# Sheet1.net
KiCad netlist of a schematic drawn in Altium Designer
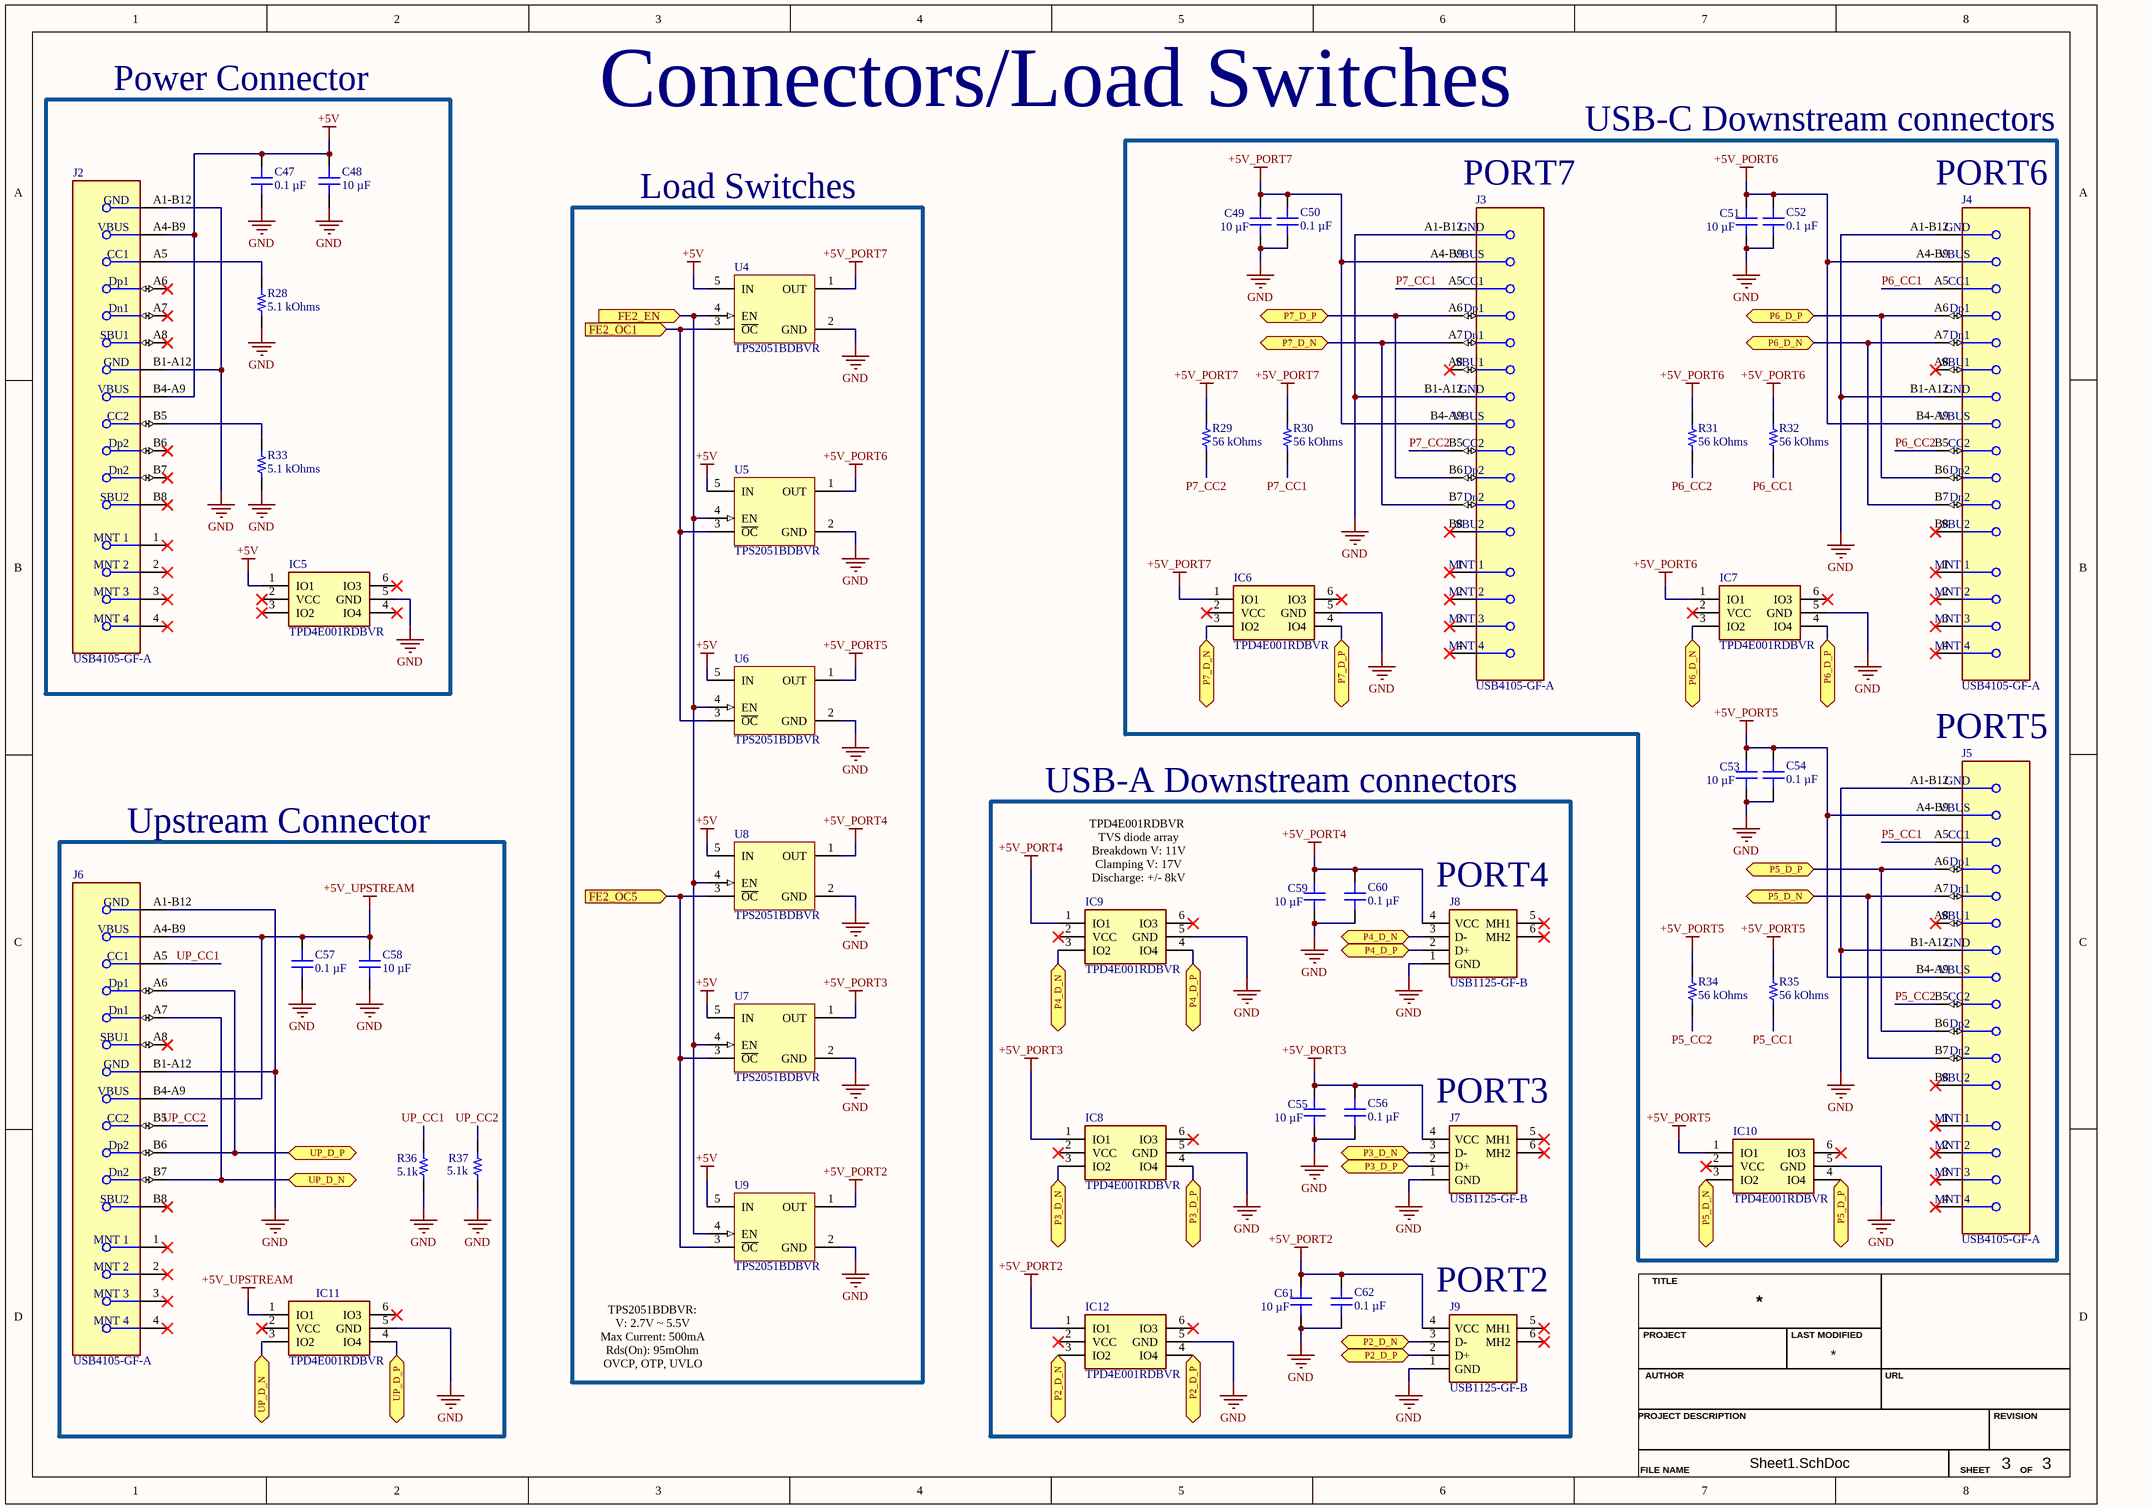
[diagram p0: Sheet1.SchDoc]

(export (version "E")
  (design (tool "Eeschema 10.0.6"))
  (components
    (comp (ref "C47")
      (value "0.1 µF")
      (footprint "CAP 0603_1608")
      (description "CAP CER 0.1UF 50V X7R 0603")
      (fields
        (field (name "PART NUMBER") "GCJ188R71H104KA12D")
        (field (name "CAPACITANCE") "0.1 µF")
        (field (name "MANUFACTURER") "Murata Electronics")
      )
      (libsource (lib "Celestial Altium Library - altium_library") (part "Capacitor"))
    )
    (comp (ref "C48")
      (value "10 µF")
      (footprint "MURATA GRM21B 0805_2012")
      (description "CAP CER 10UF 25V X5R 0805")
      (fields
        (field (name "PART NUMBER") "GRM21BR61E106KA73K")
        (field (name "CAPACITANCE") "10 µF")
        (field (name "MANUFACTURER") "Murata Electronics")
      )
      (libsource (lib "Celestial Altium Library - altium_library") (part "Capacitor"))
    )
    (comp (ref "C49")
      (value "10 µF")
      (footprint "MURATA GRM21B 0805_2012")
      (description "CAP CER 10UF 25V X5R 0805")
      (fields
        (field (name "PART NUMBER") "GRM21BR61E106KA73K")
        (field (name "CAPACITANCE") "10 µF")
        (field (name "MANUFACTURER") "Murata Electronics")
      )
      (libsource (lib "Celestial Altium Library - altium_library") (part "Capacitor"))
    )
    (comp (ref "C50")
      (value "0.1 µF")
      (footprint "CAP 0603_1608")
      (description "CAP CER 0.1UF 50V X7R 0603")
      (fields
        (field (name "PART NUMBER") "GCJ188R71H104KA12D")
        (field (name "CAPACITANCE") "0.1 µF")
        (field (name "MANUFACTURER") "Murata Electronics")
      )
      (libsource (lib "Celestial Altium Library - altium_library") (part "Capacitor"))
    )
    (comp (ref "C51")
      (value "10 µF")
      (footprint "MURATA GRM21B 0805_2012")
      (description "CAP CER 10UF 25V X5R 0805")
      (fields
        (field (name "PART NUMBER") "GRM21BR61E106KA73K")
        (field (name "CAPACITANCE") "10 µF")
        (field (name "MANUFACTURER") "Murata Electronics")
      )
      (libsource (lib "Celestial Altium Library - altium_library") (part "Capacitor"))
    )
    (comp (ref "C52")
      (value "0.1 µF")
      (footprint "CAP 0603_1608")
      (description "CAP CER 0.1UF 50V X7R 0603")
      (fields
        (field (name "PART NUMBER") "GCJ188R71H104KA12D")
        (field (name "CAPACITANCE") "0.1 µF")
        (field (name "MANUFACTURER") "Murata Electronics")
      )
      (libsource (lib "Celestial Altium Library - altium_library") (part "Capacitor"))
    )
    (comp (ref "C53")
      (value "10 µF")
      (footprint "MURATA GRM21B 0805_2012")
      (description "CAP CER 10UF 25V X5R 0805")
      (fields
        (field (name "PART NUMBER") "GRM21BR61E106KA73K")
        (field (name "CAPACITANCE") "10 µF")
        (field (name "MANUFACTURER") "Murata Electronics")
      )
      (libsource (lib "Celestial Altium Library - altium_library") (part "Capacitor"))
    )
    (comp (ref "C54")
      (value "0.1 µF")
      (footprint "CAP 0603_1608")
      (description "CAP CER 0.1UF 50V X7R 0603")
      (fields
        (field (name "PART NUMBER") "GCJ188R71H104KA12D")
        (field (name "CAPACITANCE") "0.1 µF")
        (field (name "MANUFACTURER") "Murata Electronics")
      )
      (libsource (lib "Celestial Altium Library - altium_library") (part "Capacitor"))
    )
    (comp (ref "C55")
      (value "10 µF")
      (footprint "MURATA GRM21B 0805_2012")
      (description "CAP CER 10UF 25V X5R 0805")
      (fields
        (field (name "PART NUMBER") "GRM21BR61E106KA73K")
        (field (name "CAPACITANCE") "10 µF")
        (field (name "MANUFACTURER") "Murata Electronics")
      )
      (libsource (lib "Celestial Altium Library - altium_library") (part "Capacitor"))
    )
    (comp (ref "C56")
      (value "0.1 µF")
      (footprint "CAP 0603_1608")
      (description "CAP CER 0.1UF 50V X7R 0603")
      (fields
        (field (name "PART NUMBER") "GCJ188R71H104KA12D")
        (field (name "CAPACITANCE") "0.1 µF")
        (field (name "MANUFACTURER") "Murata Electronics")
      )
      (libsource (lib "Celestial Altium Library - altium_library") (part "Capacitor"))
    )
    (comp (ref "C57")
      (value "0.1 µF")
      (footprint "CAP 0603_1608")
      (description "CAP CER 0.1UF 50V X7R 0603")
      (fields
        (field (name "PART NUMBER") "GCJ188R71H104KA12D")
        (field (name "CAPACITANCE") "0.1 µF")
        (field (name "MANUFACTURER") "Murata Electronics")
      )
      (libsource (lib "Celestial Altium Library - altium_library") (part "Capacitor"))
    )
    (comp (ref "C58")
      (value "10 µF")
      (footprint "MURATA GRM21B 0805_2012")
      (description "CAP CER 10UF 25V X5R 0805")
      (fields
        (field (name "PART NUMBER") "GRM21BR61E106KA73K")
        (field (name "CAPACITANCE") "10 µF")
        (field (name "MANUFACTURER") "Murata Electronics")
      )
      (libsource (lib "Celestial Altium Library - altium_library") (part "Capacitor"))
    )
    (comp (ref "C59")
      (value "10 µF")
      (footprint "MURATA GRM21B 0805_2012")
      (description "CAP CER 10UF 25V X5R 0805")
      (fields
        (field (name "PART NUMBER") "GRM21BR61E106KA73K")
        (field (name "CAPACITANCE") "10 µF")
        (field (name "MANUFACTURER") "Murata Electronics")
      )
      (libsource (lib "Celestial Altium Library - altium_library") (part "Capacitor"))
    )
    (comp (ref "C60")
      (value "0.1 µF")
      (footprint "CAP 0603_1608")
      (description "CAP CER 0.1UF 50V X7R 0603")
      (fields
        (field (name "PART NUMBER") "GCJ188R71H104KA12D")
        (field (name "CAPACITANCE") "0.1 µF")
        (field (name "MANUFACTURER") "Murata Electronics")
      )
      (libsource (lib "Celestial Altium Library - altium_library") (part "Capacitor"))
    )
    (comp (ref "C61")
      (value "10 µF")
      (footprint "MURATA GRM21B 0805_2012")
      (description "CAP CER 10UF 25V X5R 0805")
      (fields
        (field (name "PART NUMBER") "GRM21BR61E106KA73K")
        (field (name "CAPACITANCE") "10 µF")
        (field (name "MANUFACTURER") "Murata Electronics")
      )
      (libsource (lib "Celestial Altium Library - altium_library") (part "Capacitor"))
    )
    (comp (ref "C62")
      (value "0.1 µF")
      (footprint "CAP 0603_1608")
      (description "CAP CER 0.1UF 50V X7R 0603")
      (fields
        (field (name "PART NUMBER") "GCJ188R71H104KA12D")
        (field (name "CAPACITANCE") "0.1 µF")
        (field (name "MANUFACTURER") "Murata Electronics")
      )
      (libsource (lib "Celestial Altium Library - altium_library") (part "Capacitor"))
    )
    (comp (ref "IC5")
      (value "TPD4E001RDBVR")
      (footprint "SamacSys:SOT95P280X145-6N")
      (description "Integrated Circuit")
      (fields (field (name "MOUSER PART NUMBER") "595-TPD4E001RDBVR"))
      (libsource (lib "*") (part "TPD4E001RDBVR"))
    )
    (comp (ref "IC6")
      (value "TPD4E001RDBVR")
      (footprint "SamacSys:SOT95P280X145-6N")
      (description "Integrated Circuit")
      (fields (field (name "MOUSER PART NUMBER") "595-TPD4E001RDBVR"))
      (libsource (lib "*") (part "TPD4E001RDBVR"))
    )
    (comp (ref "IC7")
      (value "TPD4E001RDBVR")
      (footprint "SamacSys:SOT95P280X145-6N")
      (description "Integrated Circuit")
      (fields (field (name "MOUSER PART NUMBER") "595-TPD4E001RDBVR"))
      (libsource (lib "*") (part "TPD4E001RDBVR"))
    )
    (comp (ref "IC8")
      (value "TPD4E001RDBVR")
      (footprint "SamacSys:SOT95P280X145-6N")
      (description "Integrated Circuit")
      (fields (field (name "MOUSER PART NUMBER") "595-TPD4E001RDBVR"))
      (libsource (lib "*") (part "TPD4E001RDBVR"))
    )
    (comp (ref "IC9")
      (value "TPD4E001RDBVR")
      (footprint "SamacSys:SOT95P280X145-6N")
      (description "Integrated Circuit")
      (fields (field (name "MOUSER PART NUMBER") "595-TPD4E001RDBVR"))
      (libsource (lib "*") (part "TPD4E001RDBVR"))
    )
    (comp (ref "IC10")
      (value "TPD4E001RDBVR")
      (footprint "SamacSys:SOT95P280X145-6N")
      (description "Integrated Circuit")
      (fields (field (name "MOUSER PART NUMBER") "595-TPD4E001RDBVR"))
      (libsource (lib "*") (part "TPD4E001RDBVR"))
    )
    (comp (ref "IC11")
      (value "TPD4E001RDBVR")
      (footprint "SamacSys:SOT95P280X145-6N")
      (description "Integrated Circuit")
      (fields (field (name "MOUSER PART NUMBER") "595-TPD4E001RDBVR"))
      (libsource (lib "*") (part "TPD4E001RDBVR"))
    )
    (comp (ref "IC12")
      (value "TPD4E001RDBVR")
      (footprint "SamacSys:SOT95P280X145-6N")
      (description "Integrated Circuit")
      (fields (field (name "MOUSER PART NUMBER") "595-TPD4E001RDBVR"))
      (libsource (lib "*") (part "TPD4E001RDBVR"))
    )
    (comp (ref "J2")
      (value "USB4105-GF-A")
      (footprint "FP-USB4105-GF-A-MFG")
      (description "Conn USB 2.0 Type C RCP 24 POS 0.3mm/0.5mm Solder RA SMD 24 Terminal 1 Port T/R")
      (libsource (lib "") (part "e7c17a616881a82b79941196b4bec10_1"))
    )
    (comp (ref "J3")
      (value "USB4105-GF-A")
      (footprint "FP-USB4105-GF-A-MFG")
      (description "Conn USB 2.0 Type C RCP 24 POS 0.3mm/0.5mm Solder RA SMD 24 Terminal 1 Port T/R")
      (libsource (lib "Sandor Lazar") (part "e7c17a616881a82b79941196b4bec10"))
    )
    (comp (ref "J4")
      (value "USB4105-GF-A")
      (footprint "FP-USB4105-GF-A-MFG")
      (description "Conn USB 2.0 Type C RCP 24 POS 0.3mm/0.5mm Solder RA SMD 24 Terminal 1 Port T/R")
      (libsource (lib "Sandor Lazar") (part "e7c17a616881a82b79941196b4bec10"))
    )
    (comp (ref "J5")
      (value "USB4105-GF-A")
      (footprint "FP-USB4105-GF-A-MFG")
      (description "Conn USB 2.0 Type C RCP 24 POS 0.3mm/0.5mm Solder RA SMD 24 Terminal 1 Port T/R")
      (libsource (lib "Sandor Lazar") (part "e7c17a616881a82b79941196b4bec10"))
    )
    (comp (ref "J6")
      (value "USB4105-GF-A")
      (footprint "FP-USB4105-GF-A-MFG")
      (description "Conn USB 2.0 Type C RCP 24 POS 0.3mm/0.5mm Solder RA SMD 24 Terminal 1 Port T/R")
      (libsource (lib "") (part "e7c17a616881a82b79941196b4bec10_1"))
    )
    (comp (ref "J7")
      (value "USB1125-GF-B")
      (footprint "SamacSys:USB1125GFB")
      (description "Connector")
      (fields (field (name "MOUSER PART NUMBER") "640-USB1125-GF-B"))
      (libsource (lib "SamacSys") (part "USB1125-GF-B"))
    )
    (comp (ref "J8")
      (value "USB1125-GF-B")
      (footprint "SamacSys:USB1125GFB")
      (description "Connector")
      (fields (field (name "MOUSER PART NUMBER") "640-USB1125-GF-B"))
      (libsource (lib "SamacSys") (part "USB1125-GF-B"))
    )
    (comp (ref "J9")
      (value "USB1125-GF-B")
      (footprint "SamacSys:USB1125GFB")
      (description "Connector")
      (fields (field (name "MOUSER PART NUMBER") "640-USB1125-GF-B"))
      (libsource (lib "SamacSys") (part "USB1125-GF-B"))
    )
    (comp (ref "R28")
      (value "5.1 kOhms")
      (footprint "KOA RES RK73 RN73 0603_1608")
      (description "RESISTOR")
      (fields
        (field (name "PART NUMBER") "RK73B1JTTDD512J")
        (field (name "MANUFACTURER") "KOA Speer Electronics, Inc.")
      )
      (libsource (lib "Celestial Altium Library - altium_library") (part "Resistor"))
    )
    (comp (ref "R29")
      (value "56 kOhms")
      (footprint "YAGEO RES 0603_1608")
      (description "RES 56K OHM 5% 1/10W 0603")
      (fields (field (name "PART NUMBER") "RC0603JR-0756KL") (field (name "MANUFACTURER") "Yageo"))
      (libsource (lib "Celestial Altium Library - altium_library") (part "Resistor"))
    )
    (comp (ref "R30")
      (value "56 kOhms")
      (footprint "YAGEO RES 0603_1608")
      (description "RES 56K OHM 5% 1/10W 0603")
      (fields (field (name "PART NUMBER") "RC0603JR-0756KL") (field (name "MANUFACTURER") "Yageo"))
      (libsource (lib "Celestial Altium Library - altium_library") (part "Resistor"))
    )
    (comp (ref "R31")
      (value "56 kOhms")
      (footprint "YAGEO RES 0603_1608")
      (description "RES 56K OHM 5% 1/10W 0603")
      (fields (field (name "PART NUMBER") "RC0603JR-0756KL") (field (name "MANUFACTURER") "Yageo"))
      (libsource (lib "Celestial Altium Library - altium_library") (part "Resistor"))
    )
    (comp (ref "R32")
      (value "56 kOhms")
      (footprint "YAGEO RES 0603_1608")
      (description "RES 56K OHM 5% 1/10W 0603")
      (fields (field (name "PART NUMBER") "RC0603JR-0756KL") (field (name "MANUFACTURER") "Yageo"))
      (libsource (lib "Celestial Altium Library - altium_library") (part "Resistor"))
    )
    (comp (ref "R33")
      (value "5.1 kOhms")
      (footprint "KOA RES RK73 RN73 0603_1608")
      (description "RESISTOR")
      (fields
        (field (name "PART NUMBER") "RK73B1JTTDD512J")
        (field (name "MANUFACTURER") "KOA Speer Electronics, Inc.")
      )
      (libsource (lib "Celestial Altium Library - altium_library") (part "Resistor"))
    )
    (comp (ref "R34")
      (value "56 kOhms")
      (footprint "YAGEO RES 0603_1608")
      (description "RES 56K OHM 5% 1/10W 0603")
      (fields (field (name "PART NUMBER") "RC0603JR-0756KL") (field (name "MANUFACTURER") "Yageo"))
      (libsource (lib "Celestial Altium Library - altium_library") (part "Resistor"))
    )
    (comp (ref "R35")
      (value "56 kOhms")
      (footprint "YAGEO RES 0603_1608")
      (description "RES 56K OHM 5% 1/10W 0603")
      (fields (field (name "PART NUMBER") "RC0603JR-0756KL") (field (name "MANUFACTURER") "Yageo"))
      (libsource (lib "Celestial Altium Library - altium_library") (part "Resistor"))
    )
    (comp (ref "R36")
      (value "5.1k")
      (footprint "KOA RES RK73 RN73 0603_1608")
      (description "RESISTOR")
      (fields
        (field (name "PART NUMBER") "RK73B1JTTDD512J")
        (field (name "MANUFACTURER") "KOA Speer Electronics, Inc.")
      )
      (libsource (lib "Celestial Altium Library - altium_library") (part "Resistor"))
    )
    (comp (ref "R37")
      (value "5.1k")
      (footprint "KOA RES RK73 RN73 0603_1608")
      (description "RESISTOR")
      (fields
        (field (name "PART NUMBER") "RK73B1JTTDD512J")
        (field (name "MANUFACTURER") "KOA Speer Electronics, Inc.")
      )
      (libsource (lib "Celestial Altium Library - altium_library") (part "Resistor"))
    )
    (comp (ref "U4")
      (value "TPS2051BDBVR")
      (footprint "DBV0005A_L")
      (description "0.5A loading, 2.7-5.5V, 70mΩ USB power switch, active-high 5-SOT-23 -40 to 125")
      (libsource (lib "Sandor Lazar") (part "TI-TPS2051BDBV5"))
    )
    (comp (ref "U5")
      (value "TPS2051BDBVR")
      (footprint "DBV0005A_L")
      (description "0.5A loading, 2.7-5.5V, 70mΩ USB power switch, active-high 5-SOT-23 -40 to 125")
      (libsource (lib "Sandor Lazar") (part "TI-TPS2051BDBV5"))
    )
    (comp (ref "U6")
      (value "TPS2051BDBVR")
      (footprint "DBV0005A_L")
      (description "0.5A loading, 2.7-5.5V, 70mΩ USB power switch, active-high 5-SOT-23 -40 to 125")
      (libsource (lib "Sandor Lazar") (part "TI-TPS2051BDBV5"))
    )
    (comp (ref "U7")
      (value "TPS2051BDBVR")
      (footprint "DBV0005A_L")
      (description "0.5A loading, 2.7-5.5V, 70mΩ USB power switch, active-high 5-SOT-23 -40 to 125")
      (libsource (lib "Sandor Lazar") (part "TI-TPS2051BDBV5"))
    )
    (comp (ref "U8")
      (value "TPS2051BDBVR")
      (footprint "DBV0005A_L")
      (description "0.5A loading, 2.7-5.5V, 70mΩ USB power switch, active-high 5-SOT-23 -40 to 125")
      (libsource (lib "Sandor Lazar") (part "TI-TPS2051BDBV5"))
    )
    (comp (ref "U9")
      (value "TPS2051BDBVR")
      (footprint "DBV0005A_L")
      (description "0.5A loading, 2.7-5.5V, 70mΩ USB power switch, active-high 5-SOT-23 -40 to 125")
      (libsource (lib "Sandor Lazar") (part "TI-TPS2051BDBV5"))
    )
  )
  (nets
    (net (code "1") (name "+5V") (class "Default")
      (node (ref "C47") (pin "2") (pinfunction "2_2") (pintype "passive"))
      (node (ref "C48") (pin "2") (pinfunction "2_2") (pintype "passive"))
      (node (ref "IC5") (pin "1") (pinfunction "IO1_1") (pintype "passive"))
      (node (ref "J2") (pin "A4-B9") (pinfunction "VBUS_A4-B9") (pintype "power_in"))
      (node (ref "J2") (pin "B4-A9") (pinfunction "VBUS_B4-A9") (pintype "power_in"))
      (node (ref "U4") (pin "5") (pinfunction "IN_5") (pintype "power_in"))
      (node (ref "U5") (pin "5") (pinfunction "IN_5") (pintype "power_in"))
      (node (ref "U6") (pin "5") (pinfunction "IN_5") (pintype "power_in"))
      (node (ref "U7") (pin "5") (pinfunction "IN_5") (pintype "power_in"))
      (node (ref "U8") (pin "5") (pinfunction "IN_5") (pintype "power_in"))
      (node (ref "U9") (pin "5") (pinfunction "IN_5") (pintype "power_in"))
    )
    (net (code "2") (name "+5V_PORT2") (class "Default")
      (node (ref "C61") (pin "2") (pinfunction "2_2") (pintype "passive"))
      (node (ref "C62") (pin "2") (pinfunction "2_2") (pintype "passive"))
      (node (ref "IC12") (pin "1") (pinfunction "IO1_1") (pintype "passive"))
      (node (ref "J9") (pin "4") (pinfunction "VCC_4") (pintype "passive"))
      (node (ref "U9") (pin "1") (pinfunction "OUT_1") (pintype "power_in"))
    )
    (net (code "3") (name "+5V_PORT3") (class "Default")
      (node (ref "C55") (pin "2") (pinfunction "2_2") (pintype "passive"))
      (node (ref "C56") (pin "2") (pinfunction "2_2") (pintype "passive"))
      (node (ref "IC8") (pin "1") (pinfunction "IO1_1") (pintype "passive"))
      (node (ref "J7") (pin "4") (pinfunction "VCC_4") (pintype "passive"))
      (node (ref "U7") (pin "1") (pinfunction "OUT_1") (pintype "power_in"))
    )
    (net (code "4") (name "+5V_PORT4") (class "Default")
      (node (ref "C59") (pin "2") (pinfunction "2_2") (pintype "passive"))
      (node (ref "C60") (pin "2") (pinfunction "2_2") (pintype "passive"))
      (node (ref "IC9") (pin "1") (pinfunction "IO1_1") (pintype "passive"))
      (node (ref "J8") (pin "4") (pinfunction "VCC_4") (pintype "passive"))
      (node (ref "U8") (pin "1") (pinfunction "OUT_1") (pintype "power_in"))
    )
    (net (code "5") (name "+5V_PORT5") (class "Default")
      (node (ref "C53") (pin "2") (pinfunction "2_2") (pintype "passive"))
      (node (ref "C54") (pin "2") (pinfunction "2_2") (pintype "passive"))
      (node (ref "IC10") (pin "1") (pinfunction "IO1_1") (pintype "passive"))
      (node (ref "J5") (pin "A4-B9") (pinfunction "VBUS_A4-B9") (pintype "power_in"))
      (node (ref "J5") (pin "B4-A9") (pinfunction "VBUS_B4-A9") (pintype "power_in"))
      (node (ref "R34") (pin "2") (pinfunction "2_2") (pintype "passive"))
      (node (ref "R35") (pin "2") (pinfunction "2_2") (pintype "passive"))
      (node (ref "U6") (pin "1") (pinfunction "OUT_1") (pintype "power_in"))
    )
    (net (code "6") (name "+5V_PORT6") (class "Default")
      (node (ref "C51") (pin "2") (pinfunction "2_2") (pintype "passive"))
      (node (ref "C52") (pin "2") (pinfunction "2_2") (pintype "passive"))
      (node (ref "IC7") (pin "1") (pinfunction "IO1_1") (pintype "passive"))
      (node (ref "J4") (pin "A4-B9") (pinfunction "VBUS_A4-B9") (pintype "power_in"))
      (node (ref "J4") (pin "B4-A9") (pinfunction "VBUS_B4-A9") (pintype "power_in"))
      (node (ref "R31") (pin "2") (pinfunction "2_2") (pintype "passive"))
      (node (ref "R32") (pin "2") (pinfunction "2_2") (pintype "passive"))
      (node (ref "U5") (pin "1") (pinfunction "OUT_1") (pintype "power_in"))
    )
    (net (code "7") (name "+5V_PORT7") (class "Default")
      (node (ref "C49") (pin "2") (pinfunction "2_2") (pintype "passive"))
      (node (ref "C50") (pin "2") (pinfunction "2_2") (pintype "passive"))
      (node (ref "IC6") (pin "1") (pinfunction "IO1_1") (pintype "passive"))
      (node (ref "J3") (pin "A4-B9") (pinfunction "VBUS_A4-B9") (pintype "power_in"))
      (node (ref "J3") (pin "B4-A9") (pinfunction "VBUS_B4-A9") (pintype "power_in"))
      (node (ref "R29") (pin "2") (pinfunction "2_2") (pintype "passive"))
      (node (ref "R30") (pin "2") (pinfunction "2_2") (pintype "passive"))
      (node (ref "U4") (pin "1") (pinfunction "OUT_1") (pintype "power_in"))
    )
    (net (code "8") (name "+5V_UPSTREAM") (class "Default")
      (node (ref "C57") (pin "2") (pinfunction "2_2") (pintype "passive"))
      (node (ref "C58") (pin "2") (pinfunction "2_2") (pintype "passive"))
      (node (ref "IC11") (pin "1") (pinfunction "IO1_1") (pintype "passive"))
      (node (ref "J6") (pin "A4-B9") (pinfunction "VBUS_A4-B9") (pintype "power_in"))
      (node (ref "J6") (pin "B4-A9") (pinfunction "VBUS_B4-A9") (pintype "power_in"))
    )
    (net (code "9") (name "/FE2_EN") (class "Default")
      (node (ref "U4") (pin "4") (pinfunction "EN_4") (pintype "input"))
      (node (ref "U5") (pin "4") (pinfunction "EN_4") (pintype "input"))
      (node (ref "U6") (pin "4") (pinfunction "EN_4") (pintype "input"))
      (node (ref "U7") (pin "4") (pinfunction "EN_4") (pintype "input"))
      (node (ref "U8") (pin "4") (pinfunction "EN_4") (pintype "input"))
      (node (ref "U9") (pin "4") (pinfunction "EN_4") (pintype "input"))
    )
    (net (code "10") (name "/FE2_OC1") (class "Default")
      (node (ref "U4") (pin "3") (pinfunction "~{OC}_3") (pintype "passive"))
      (node (ref "U5") (pin "3") (pinfunction "~{OC}_3") (pintype "passive"))
      (node (ref "U6") (pin "3") (pinfunction "~{OC}_3") (pintype "passive"))
    )
    (net (code "11") (name "/FE2_OC5") (class "Default")
      (node (ref "U7") (pin "3") (pinfunction "~{OC}_3") (pintype "passive"))
      (node (ref "U8") (pin "3") (pinfunction "~{OC}_3") (pintype "passive"))
      (node (ref "U9") (pin "3") (pinfunction "~{OC}_3") (pintype "passive"))
    )
    (net (code "12") (name "/P2_D_N") (class "Default")
      (node (ref "IC12") (pin "3") (pinfunction "IO2_3") (pintype "passive"))
      (node (ref "J9") (pin "3") (pinfunction "D-_3") (pintype "passive"))
    )
    (net (code "13") (name "/P2_D_P") (class "Default")
      (node (ref "IC12") (pin "4") (pinfunction "IO4_4") (pintype "passive"))
      (node (ref "J9") (pin "2") (pinfunction "D+_2") (pintype "passive"))
    )
    (net (code "14") (name "/P3_D_N") (class "Default")
      (node (ref "IC8") (pin "3") (pinfunction "IO2_3") (pintype "passive"))
      (node (ref "J7") (pin "3") (pinfunction "D-_3") (pintype "passive"))
    )
    (net (code "15") (name "/P3_D_P") (class "Default")
      (node (ref "IC8") (pin "4") (pinfunction "IO4_4") (pintype "passive"))
      (node (ref "J7") (pin "2") (pinfunction "D+_2") (pintype "passive"))
    )
    (net (code "16") (name "/P4_D_N") (class "Default")
      (node (ref "IC9") (pin "3") (pinfunction "IO2_3") (pintype "passive"))
      (node (ref "J8") (pin "3") (pinfunction "D-_3") (pintype "passive"))
    )
    (net (code "17") (name "/P4_D_P") (class "Default")
      (node (ref "IC9") (pin "4") (pinfunction "IO4_4") (pintype "passive"))
      (node (ref "J8") (pin "2") (pinfunction "D+_2") (pintype "passive"))
    )
    (net (code "18") (name "/P5_CC1") (class "Default")
      (node (ref "J5") (pin "A5") (pinfunction "CC1_A5") (pintype "power_in"))
      (node (ref "R35") (pin "1") (pinfunction "1_1") (pintype "passive"))
    )
    (net (code "19") (name "/P5_CC2") (class "Default")
      (node (ref "J5") (pin "B5") (pinfunction "CC2_B5") (pintype "bidirectional"))
      (node (ref "R34") (pin "1") (pinfunction "1_1") (pintype "passive"))
    )
    (net (code "20") (name "/P5_D_N") (class "Default")
      (node (ref "IC10") (pin "3") (pinfunction "IO2_3") (pintype "passive"))
      (node (ref "J5") (pin "A7") (pinfunction "Dn1_A7") (pintype "bidirectional"))
      (node (ref "J5") (pin "B7") (pinfunction "Dn2_B7") (pintype "bidirectional"))
    )
    (net (code "21") (name "/P5_D_P") (class "Default")
      (node (ref "IC10") (pin "4") (pinfunction "IO4_4") (pintype "passive"))
      (node (ref "J5") (pin "A6") (pinfunction "Dp1_A6") (pintype "bidirectional"))
      (node (ref "J5") (pin "B6") (pinfunction "Dp2_B6") (pintype "bidirectional"))
    )
    (net (code "22") (name "/P6_CC1") (class "Default")
      (node (ref "J4") (pin "A5") (pinfunction "CC1_A5") (pintype "power_in"))
      (node (ref "R32") (pin "1") (pinfunction "1_1") (pintype "passive"))
    )
    (net (code "23") (name "/P6_CC2") (class "Default")
      (node (ref "J4") (pin "B5") (pinfunction "CC2_B5") (pintype "bidirectional"))
      (node (ref "R31") (pin "1") (pinfunction "1_1") (pintype "passive"))
    )
    (net (code "24") (name "/P6_D_N") (class "Default")
      (node (ref "IC7") (pin "3") (pinfunction "IO2_3") (pintype "passive"))
      (node (ref "J4") (pin "A7") (pinfunction "Dn1_A7") (pintype "bidirectional"))
      (node (ref "J4") (pin "B7") (pinfunction "Dn2_B7") (pintype "bidirectional"))
    )
    (net (code "25") (name "/P6_D_P") (class "Default")
      (node (ref "IC7") (pin "4") (pinfunction "IO4_4") (pintype "passive"))
      (node (ref "J4") (pin "A6") (pinfunction "Dp1_A6") (pintype "bidirectional"))
      (node (ref "J4") (pin "B6") (pinfunction "Dp2_B6") (pintype "bidirectional"))
    )
    (net (code "26") (name "/P7_CC1") (class "Default")
      (node (ref "J3") (pin "A5") (pinfunction "CC1_A5") (pintype "power_in"))
      (node (ref "R30") (pin "1") (pinfunction "1_1") (pintype "passive"))
    )
    (net (code "27") (name "/P7_CC2") (class "Default")
      (node (ref "J3") (pin "B5") (pinfunction "CC2_B5") (pintype "bidirectional"))
      (node (ref "R29") (pin "1") (pinfunction "1_1") (pintype "passive"))
    )
    (net (code "28") (name "/P7_D_N") (class "Default")
      (node (ref "IC6") (pin "3") (pinfunction "IO2_3") (pintype "passive"))
      (node (ref "J3") (pin "A7") (pinfunction "Dn1_A7") (pintype "bidirectional"))
      (node (ref "J3") (pin "B7") (pinfunction "Dn2_B7") (pintype "bidirectional"))
    )
    (net (code "29") (name "/P7_D_P") (class "Default")
      (node (ref "IC6") (pin "4") (pinfunction "IO4_4") (pintype "passive"))
      (node (ref "J3") (pin "A6") (pinfunction "Dp1_A6") (pintype "bidirectional"))
      (node (ref "J3") (pin "B6") (pinfunction "Dp2_B6") (pintype "bidirectional"))
    )
    (net (code "30") (name "/UP_CC1") (class "Default")
      (node (ref "J6") (pin "A5") (pinfunction "CC1_A5") (pintype "power_in"))
      (node (ref "R36") (pin "2") (pinfunction "2_2") (pintype "passive"))
    )
    (net (code "31") (name "/UP_CC2") (class "Default")
      (node (ref "J6") (pin "B5") (pinfunction "CC2_B5") (pintype "bidirectional"))
      (node (ref "R37") (pin "2") (pinfunction "2_2") (pintype "passive"))
    )
    (net (code "32") (name "/UP_D_N") (class "Default")
      (node (ref "IC11") (pin "3") (pinfunction "IO2_3") (pintype "passive"))
      (node (ref "J6") (pin "A7") (pinfunction "Dn1_A7") (pintype "bidirectional"))
      (node (ref "J6") (pin "B7") (pinfunction "Dn2_B7") (pintype "bidirectional"))
    )
    (net (code "33") (name "/UP_D_P") (class "Default")
      (node (ref "IC11") (pin "4") (pinfunction "IO4_4") (pintype "passive"))
      (node (ref "J6") (pin "A6") (pinfunction "Dp1_A6") (pintype "bidirectional"))
      (node (ref "J6") (pin "B6") (pinfunction "Dp2_B6") (pintype "bidirectional"))
    )
    (net (code "34") (name "GND") (class "Default")
      (node (ref "C47") (pin "1") (pinfunction "1_1") (pintype "passive"))
      (node (ref "C48") (pin "1") (pinfunction "1_1") (pintype "passive"))
      (node (ref "C49") (pin "1") (pinfunction "1_1") (pintype "passive"))
      (node (ref "C50") (pin "1") (pinfunction "1_1") (pintype "passive"))
      (node (ref "C51") (pin "1") (pinfunction "1_1") (pintype "passive"))
      (node (ref "C52") (pin "1") (pinfunction "1_1") (pintype "passive"))
      (node (ref "C53") (pin "1") (pinfunction "1_1") (pintype "passive"))
      (node (ref "C54") (pin "1") (pinfunction "1_1") (pintype "passive"))
      (node (ref "C55") (pin "1") (pinfunction "1_1") (pintype "passive"))
      (node (ref "C56") (pin "1") (pinfunction "1_1") (pintype "passive"))
      (node (ref "C57") (pin "1") (pinfunction "1_1") (pintype "passive"))
      (node (ref "C58") (pin "1") (pinfunction "1_1") (pintype "passive"))
      (node (ref "C59") (pin "1") (pinfunction "1_1") (pintype "passive"))
      (node (ref "C60") (pin "1") (pinfunction "1_1") (pintype "passive"))
      (node (ref "C61") (pin "1") (pinfunction "1_1") (pintype "passive"))
      (node (ref "C62") (pin "1") (pinfunction "1_1") (pintype "passive"))
      (node (ref "IC10") (pin "5") (pinfunction "GND_5") (pintype "passive"))
      (node (ref "IC11") (pin "5") (pinfunction "GND_5") (pintype "passive"))
      (node (ref "IC12") (pin "5") (pinfunction "GND_5") (pintype "passive"))
      (node (ref "IC5") (pin "5") (pinfunction "GND_5") (pintype "passive"))
      (node (ref "IC6") (pin "5") (pinfunction "GND_5") (pintype "passive"))
      (node (ref "IC7") (pin "5") (pinfunction "GND_5") (pintype "passive"))
      (node (ref "IC8") (pin "5") (pinfunction "GND_5") (pintype "passive"))
      (node (ref "IC9") (pin "5") (pinfunction "GND_5") (pintype "passive"))
      (node (ref "J2") (pin "A1-B12") (pinfunction "GND_A1-B12") (pintype "power_in"))
      (node (ref "J2") (pin "B1-A12") (pinfunction "GND_B1-A12") (pintype "power_in"))
      (node (ref "J3") (pin "A1-B12") (pinfunction "GND_A1-B12") (pintype "power_in"))
      (node (ref "J3") (pin "B1-A12") (pinfunction "GND_B1-A12") (pintype "power_in"))
      (node (ref "J4") (pin "A1-B12") (pinfunction "GND_A1-B12") (pintype "power_in"))
      (node (ref "J4") (pin "B1-A12") (pinfunction "GND_B1-A12") (pintype "power_in"))
      (node (ref "J5") (pin "A1-B12") (pinfunction "GND_A1-B12") (pintype "power_in"))
      (node (ref "J5") (pin "B1-A12") (pinfunction "GND_B1-A12") (pintype "power_in"))
      (node (ref "J6") (pin "A1-B12") (pinfunction "GND_A1-B12") (pintype "power_in"))
      (node (ref "J6") (pin "B1-A12") (pinfunction "GND_B1-A12") (pintype "power_in"))
      (node (ref "J7") (pin "1") (pinfunction "GND_1") (pintype "passive"))
      (node (ref "J8") (pin "1") (pinfunction "GND_1") (pintype "passive"))
      (node (ref "J9") (pin "1") (pinfunction "GND_1") (pintype "passive"))
      (node (ref "R28") (pin "1") (pinfunction "1_1") (pintype "passive"))
      (node (ref "R33") (pin "1") (pinfunction "1_1") (pintype "passive"))
      (node (ref "R36") (pin "1") (pinfunction "1_1") (pintype "passive"))
      (node (ref "R37") (pin "1") (pinfunction "1_1") (pintype "passive"))
      (node (ref "U4") (pin "2") (pinfunction "GND_2") (pintype "power_in"))
      (node (ref "U5") (pin "2") (pinfunction "GND_2") (pintype "power_in"))
      (node (ref "U6") (pin "2") (pinfunction "GND_2") (pintype "power_in"))
      (node (ref "U7") (pin "2") (pinfunction "GND_2") (pintype "power_in"))
      (node (ref "U8") (pin "2") (pinfunction "GND_2") (pintype "power_in"))
      (node (ref "U9") (pin "2") (pinfunction "GND_2") (pintype "power_in"))
    )
    (net (code "35") (name "Net-(J2-CC1)") (class "Default")
      (node (ref "J2") (pin "A5") (pinfunction "CC1_A5") (pintype "power_in"))
      (node (ref "R28") (pin "2") (pinfunction "2_2") (pintype "passive"))
    )
    (net (code "36") (name "Net-(J2-CC2)") (class "Default")
      (node (ref "J2") (pin "B5") (pinfunction "CC2_B5") (pintype "bidirectional"))
      (node (ref "R33") (pin "2") (pinfunction "2_2") (pintype "passive"))
    )
    (net (code "37") (name "unconnected-(IC5-IO2-Pad3)") (class "Default")
      (node (ref "IC5") (pin "3") (pinfunction "IO2_3") (pintype "passive+no_connect"))
    )
    (net (code "38") (name "unconnected-(IC5-IO3-Pad6)") (class "Default")
      (node (ref "IC5") (pin "6") (pinfunction "IO3_6") (pintype "passive+no_connect"))
    )
    (net (code "39") (name "unconnected-(IC5-IO4-Pad4)") (class "Default")
      (node (ref "IC5") (pin "4") (pinfunction "IO4_4") (pintype "passive+no_connect"))
    )
    (net (code "40") (name "unconnected-(IC5-VCC-Pad2)") (class "Default")
      (node (ref "IC5") (pin "2") (pinfunction "VCC_2") (pintype "passive+no_connect"))
    )
    (net (code "41") (name "unconnected-(IC6-IO3-Pad6)") (class "Default")
      (node (ref "IC6") (pin "6") (pinfunction "IO3_6") (pintype "passive+no_connect"))
    )
    (net (code "42") (name "unconnected-(IC6-VCC-Pad2)") (class "Default")
      (node (ref "IC6") (pin "2") (pinfunction "VCC_2") (pintype "passive+no_connect"))
    )
    (net (code "43") (name "unconnected-(IC7-IO3-Pad6)") (class "Default")
      (node (ref "IC7") (pin "6") (pinfunction "IO3_6") (pintype "passive+no_connect"))
    )
    (net (code "44") (name "unconnected-(IC7-VCC-Pad2)") (class "Default")
      (node (ref "IC7") (pin "2") (pinfunction "VCC_2") (pintype "passive+no_connect"))
    )
    (net (code "45") (name "unconnected-(IC8-IO3-Pad6)") (class "Default")
      (node (ref "IC8") (pin "6") (pinfunction "IO3_6") (pintype "passive+no_connect"))
    )
    (net (code "46") (name "unconnected-(IC8-VCC-Pad2)") (class "Default")
      (node (ref "IC8") (pin "2") (pinfunction "VCC_2") (pintype "passive+no_connect"))
    )
    (net (code "47") (name "unconnected-(IC9-IO3-Pad6)") (class "Default")
      (node (ref "IC9") (pin "6") (pinfunction "IO3_6") (pintype "passive+no_connect"))
    )
    (net (code "48") (name "unconnected-(IC9-VCC-Pad2)") (class "Default")
      (node (ref "IC9") (pin "2") (pinfunction "VCC_2") (pintype "passive+no_connect"))
    )
    (net (code "49") (name "unconnected-(IC10-IO3-Pad6)") (class "Default")
      (node (ref "IC10") (pin "6") (pinfunction "IO3_6") (pintype "passive+no_connect"))
    )
    (net (code "50") (name "unconnected-(IC10-VCC-Pad2)") (class "Default")
      (node (ref "IC10") (pin "2") (pinfunction "VCC_2") (pintype "passive+no_connect"))
    )
    (net (code "51") (name "unconnected-(IC11-IO3-Pad6)") (class "Default")
      (node (ref "IC11") (pin "6") (pinfunction "IO3_6") (pintype "passive+no_connect"))
    )
    (net (code "52") (name "unconnected-(IC11-VCC-Pad2)") (class "Default")
      (node (ref "IC11") (pin "2") (pinfunction "VCC_2") (pintype "passive+no_connect"))
    )
    (net (code "53") (name "unconnected-(IC12-IO3-Pad6)") (class "Default")
      (node (ref "IC12") (pin "6") (pinfunction "IO3_6") (pintype "passive+no_connect"))
    )
    (net (code "54") (name "unconnected-(IC12-VCC-Pad2)") (class "Default")
      (node (ref "IC12") (pin "2") (pinfunction "VCC_2") (pintype "passive+no_connect"))
    )
    (net (code "55") (name "unconnected-(J2-Dn1-PadA7)") (class "Default")
      (node (ref "J2") (pin "A7") (pinfunction "Dn1_A7") (pintype "bidirectional+no_connect"))
    )
    (net (code "56") (name "unconnected-(J2-Dn2-PadB7)") (class "Default")
      (node (ref "J2") (pin "B7") (pinfunction "Dn2_B7") (pintype "bidirectional+no_connect"))
    )
    (net (code "57") (name "unconnected-(J2-Dp1-PadA6)") (class "Default")
      (node (ref "J2") (pin "A6") (pinfunction "Dp1_A6") (pintype "bidirectional+no_connect"))
    )
    (net (code "58") (name "unconnected-(J2-Dp2-PadB6)") (class "Default")
      (node (ref "J2") (pin "B6") (pinfunction "Dp2_B6") (pintype "bidirectional+no_connect"))
    )
    (net (code "59") (name "unconnected-(J2-MNT_1-Pad1)") (class "Default")
      (node (ref "J2") (pin "1") (pinfunction "MNT_1_1") (pintype "power_in+no_connect"))
    )
    (net (code "60") (name "unconnected-(J2-MNT_2-Pad2)") (class "Default")
      (node (ref "J2") (pin "2") (pinfunction "MNT_2_2") (pintype "power_in+no_connect"))
    )
    (net (code "61") (name "unconnected-(J2-MNT_3-Pad3)") (class "Default")
      (node (ref "J2") (pin "3") (pinfunction "MNT_3_3") (pintype "power_in+no_connect"))
    )
    (net (code "62") (name "unconnected-(J2-MNT_4-Pad4)") (class "Default")
      (node (ref "J2") (pin "4") (pinfunction "MNT_4_4") (pintype "power_in+no_connect"))
    )
    (net (code "63") (name "unconnected-(J2-SBU1-PadA8)") (class "Default")
      (node (ref "J2") (pin "A8") (pinfunction "SBU1_A8") (pintype "bidirectional+no_connect"))
    )
    (net (code "64") (name "unconnected-(J2-SBU2-PadB8)") (class "Default")
      (node (ref "J2") (pin "B8") (pinfunction "SBU2_B8") (pintype "power_in+no_connect"))
    )
    (net (code "65") (name "unconnected-(J3-MNT_1-Pad1)") (class "Default")
      (node (ref "J3") (pin "1") (pinfunction "MNT_1_1") (pintype "power_in+no_connect"))
    )
    (net (code "66") (name "unconnected-(J3-MNT_2-Pad2)") (class "Default")
      (node (ref "J3") (pin "2") (pinfunction "MNT_2_2") (pintype "power_in+no_connect"))
    )
    (net (code "67") (name "unconnected-(J3-MNT_3-Pad3)") (class "Default")
      (node (ref "J3") (pin "3") (pinfunction "MNT_3_3") (pintype "power_in+no_connect"))
    )
    (net (code "68") (name "unconnected-(J3-MNT_4-Pad4)") (class "Default")
      (node (ref "J3") (pin "4") (pinfunction "MNT_4_4") (pintype "power_in+no_connect"))
    )
    (net (code "69") (name "unconnected-(J3-SBU1-PadA8)") (class "Default")
      (node (ref "J3") (pin "A8") (pinfunction "SBU1_A8") (pintype "bidirectional+no_connect"))
    )
    (net (code "70") (name "unconnected-(J3-SBU2-PadB8)") (class "Default")
      (node (ref "J3") (pin "B8") (pinfunction "SBU2_B8") (pintype "power_in+no_connect"))
    )
    (net (code "71") (name "unconnected-(J4-MNT_1-Pad1)") (class "Default")
      (node (ref "J4") (pin "1") (pinfunction "MNT_1_1") (pintype "power_in+no_connect"))
    )
    (net (code "72") (name "unconnected-(J4-MNT_2-Pad2)") (class "Default")
      (node (ref "J4") (pin "2") (pinfunction "MNT_2_2") (pintype "power_in+no_connect"))
    )
    (net (code "73") (name "unconnected-(J4-MNT_3-Pad3)") (class "Default")
      (node (ref "J4") (pin "3") (pinfunction "MNT_3_3") (pintype "power_in+no_connect"))
    )
    (net (code "74") (name "unconnected-(J4-MNT_4-Pad4)") (class "Default")
      (node (ref "J4") (pin "4") (pinfunction "MNT_4_4") (pintype "power_in+no_connect"))
    )
    (net (code "75") (name "unconnected-(J4-SBU1-PadA8)") (class "Default")
      (node (ref "J4") (pin "A8") (pinfunction "SBU1_A8") (pintype "bidirectional+no_connect"))
    )
    (net (code "76") (name "unconnected-(J4-SBU2-PadB8)") (class "Default")
      (node (ref "J4") (pin "B8") (pinfunction "SBU2_B8") (pintype "power_in+no_connect"))
    )
    (net (code "77") (name "unconnected-(J5-MNT_1-Pad1)") (class "Default")
      (node (ref "J5") (pin "1") (pinfunction "MNT_1_1") (pintype "power_in+no_connect"))
    )
    (net (code "78") (name "unconnected-(J5-MNT_2-Pad2)") (class "Default")
      (node (ref "J5") (pin "2") (pinfunction "MNT_2_2") (pintype "power_in+no_connect"))
    )
    (net (code "79") (name "unconnected-(J5-MNT_3-Pad3)") (class "Default")
      (node (ref "J5") (pin "3") (pinfunction "MNT_3_3") (pintype "power_in+no_connect"))
    )
    (net (code "80") (name "unconnected-(J5-MNT_4-Pad4)") (class "Default")
      (node (ref "J5") (pin "4") (pinfunction "MNT_4_4") (pintype "power_in+no_connect"))
    )
    (net (code "81") (name "unconnected-(J5-SBU1-PadA8)") (class "Default")
      (node (ref "J5") (pin "A8") (pinfunction "SBU1_A8") (pintype "bidirectional+no_connect"))
    )
    (net (code "82") (name "unconnected-(J5-SBU2-PadB8)") (class "Default")
      (node (ref "J5") (pin "B8") (pinfunction "SBU2_B8") (pintype "power_in+no_connect"))
    )
    (net (code "83") (name "unconnected-(J6-MNT_1-Pad1)") (class "Default")
      (node (ref "J6") (pin "1") (pinfunction "MNT_1_1") (pintype "power_in+no_connect"))
    )
    (net (code "84") (name "unconnected-(J6-MNT_2-Pad2)") (class "Default")
      (node (ref "J6") (pin "2") (pinfunction "MNT_2_2") (pintype "power_in+no_connect"))
    )
    (net (code "85") (name "unconnected-(J6-MNT_3-Pad3)") (class "Default")
      (node (ref "J6") (pin "3") (pinfunction "MNT_3_3") (pintype "power_in+no_connect"))
    )
    (net (code "86") (name "unconnected-(J6-MNT_4-Pad4)") (class "Default")
      (node (ref "J6") (pin "4") (pinfunction "MNT_4_4") (pintype "power_in+no_connect"))
    )
    (net (code "87") (name "unconnected-(J6-SBU1-PadA8)") (class "Default")
      (node (ref "J6") (pin "A8") (pinfunction "SBU1_A8") (pintype "bidirectional+no_connect"))
    )
    (net (code "88") (name "unconnected-(J6-SBU2-PadB8)") (class "Default")
      (node (ref "J6") (pin "B8") (pinfunction "SBU2_B8") (pintype "power_in+no_connect"))
    )
    (net (code "89") (name "unconnected-(J7-MH1-Pad5)") (class "Default")
      (node (ref "J7") (pin "5") (pinfunction "MH1_5") (pintype "passive+no_connect"))
    )
    (net (code "90") (name "unconnected-(J7-MH2-Pad6)") (class "Default")
      (node (ref "J7") (pin "6") (pinfunction "MH2_6") (pintype "passive+no_connect"))
    )
    (net (code "91") (name "unconnected-(J8-MH1-Pad5)") (class "Default")
      (node (ref "J8") (pin "5") (pinfunction "MH1_5") (pintype "passive+no_connect"))
    )
    (net (code "92") (name "unconnected-(J8-MH2-Pad6)") (class "Default")
      (node (ref "J8") (pin "6") (pinfunction "MH2_6") (pintype "passive+no_connect"))
    )
    (net (code "93") (name "unconnected-(J9-MH1-Pad5)") (class "Default")
      (node (ref "J9") (pin "5") (pinfunction "MH1_5") (pintype "passive+no_connect"))
    )
    (net (code "94") (name "unconnected-(J9-MH2-Pad6)") (class "Default")
      (node (ref "J9") (pin "6") (pinfunction "MH2_6") (pintype "passive+no_connect"))
    )
  )
)
